# eCog100_ESP8266_Wifi.net
KiCad netlist of a schematic drawn in EAGLE
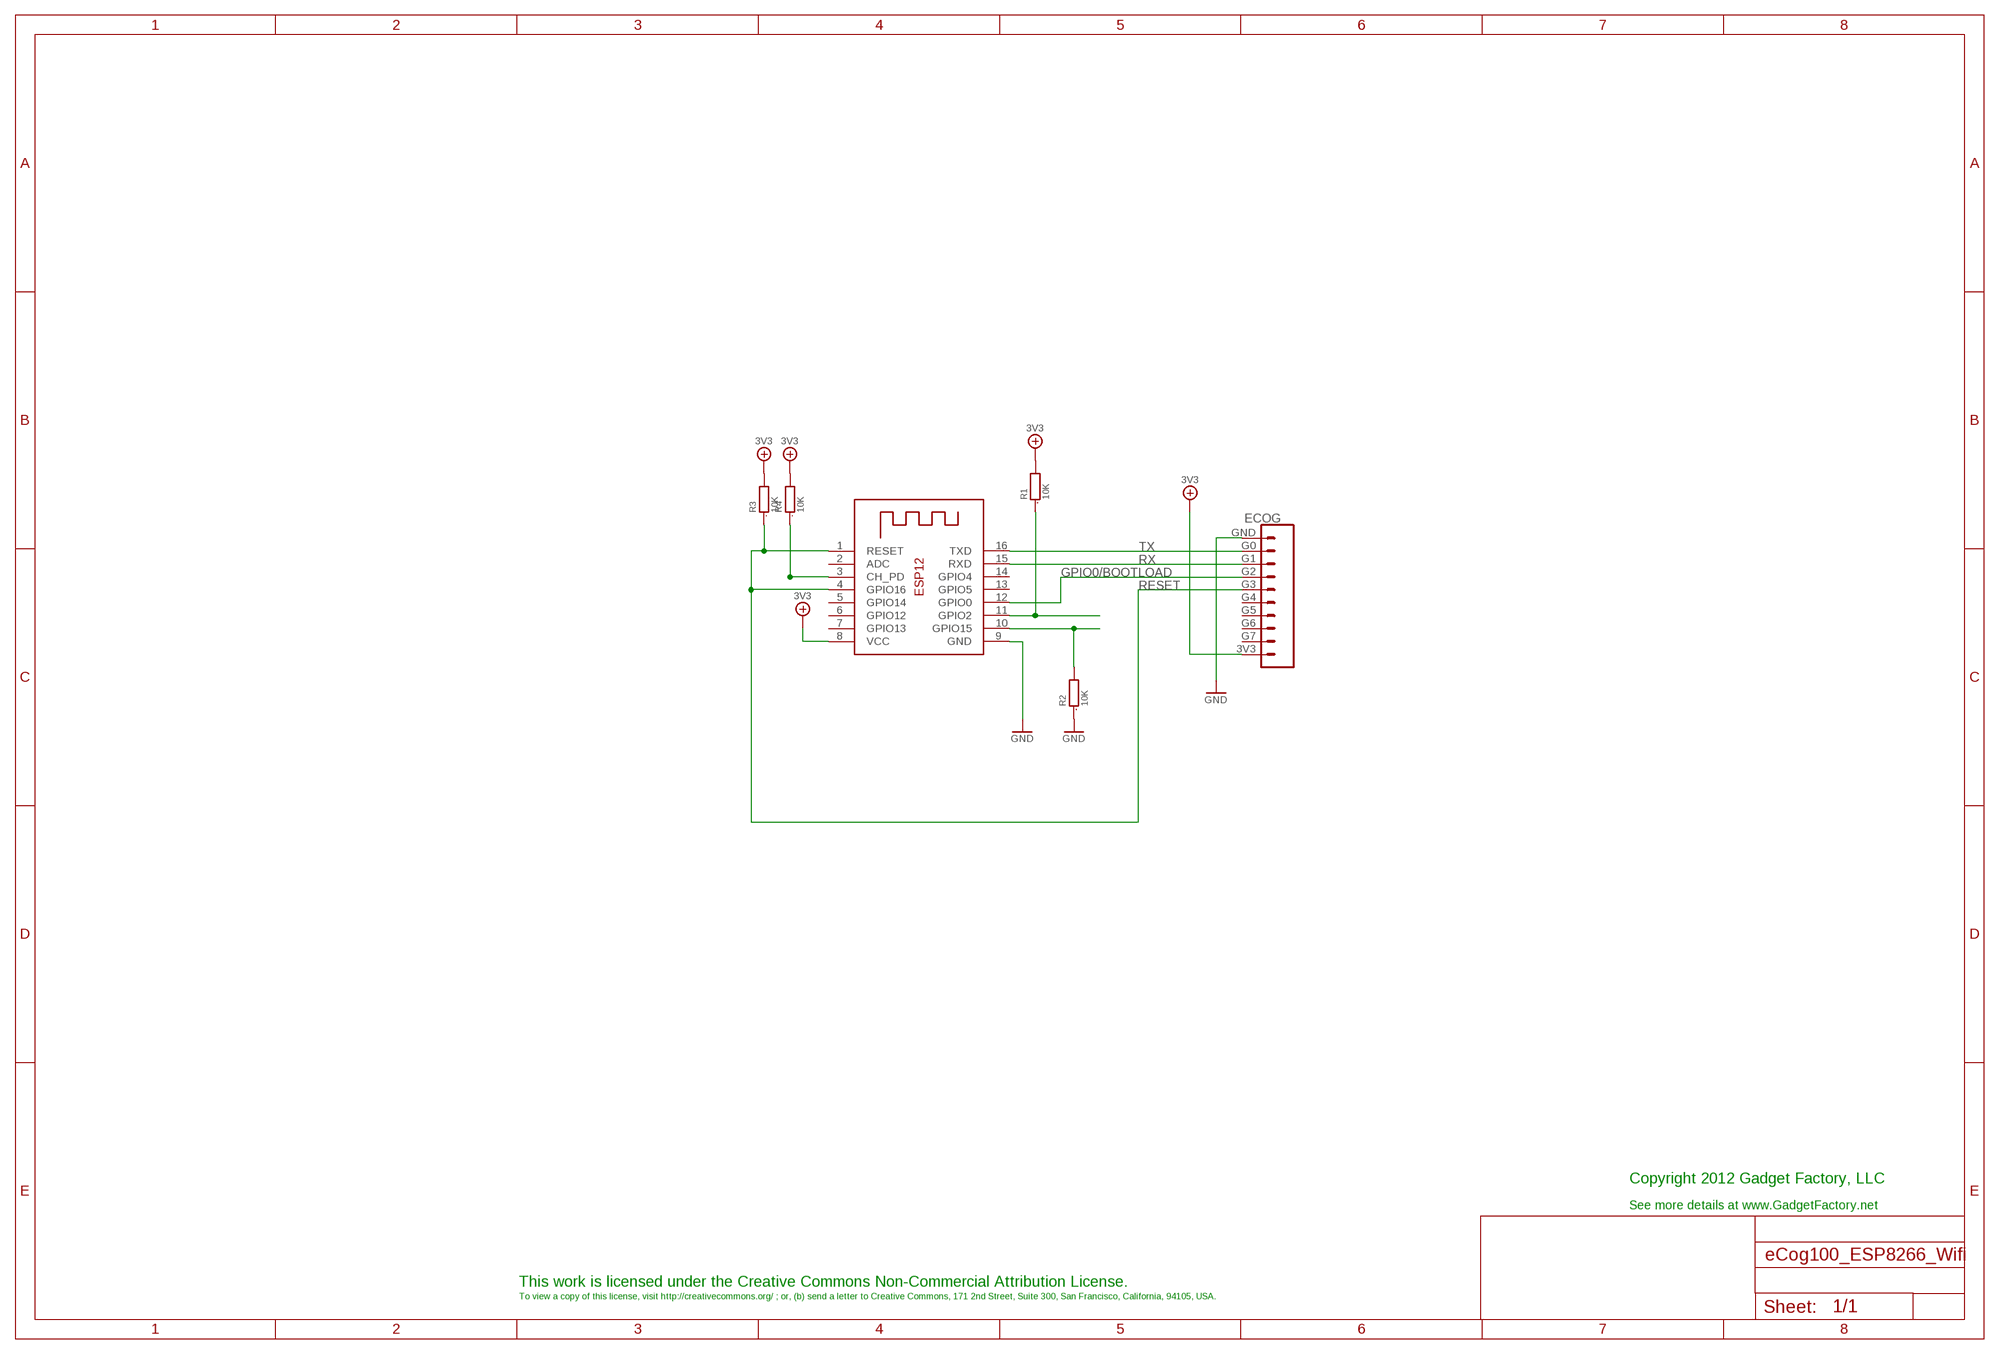
[diagram p0: schematic, sheet 1]

(export (version "E")
  (design (tool "Eeschema 10.0.6"))
  (components
    (comp (ref "ECOG")
      (value "ECOG_GENERAL_ROWECOG_GENERAL_SMD")
      (footprint "eagle-import:ECOG_GENERAL_SMD")
      (libsource (lib "eagle-import") (part "ECOG_GENERAL_ROWECOG_GENERAL_SMD"))
    )
    (comp (ref "R1")
      (value "10K")
      (footprint "eagle-import:0805")
      (libsource (lib "eagle-import") (part "R0805"))
    )
    (comp (ref "R2")
      (value "10K")
      (footprint "eagle-import:0805")
      (libsource (lib "eagle-import") (part "R0805"))
    )
    (comp (ref "R3")
      (value "10K")
      (footprint "eagle-import:0805")
      (libsource (lib "eagle-import") (part "R0805"))
    )
    (comp (ref "R4")
      (value "10K")
      (footprint "eagle-import:0805")
      (libsource (lib "eagle-import") (part "R0805"))
    )
    (comp (ref "X1")
      (value "ESP-12")
      (footprint "eagle-import:ESP-12")
      (libsource (lib "eagle-import") (part "ESP-12"))
    )
  )
  (nets
    (net (code "1") (name "/GPIO0{slash}BOOTLOAD") (class "Default")
      (node (ref "ECOG") (pin "G2") (pinfunction "G2_G2") (pintype "passive"))
      (node (ref "X1") (pin "12") (pinfunction "GPIO0_12") (pintype "bidirectional"))
    )
    (net (code "2") (name "/RESET") (class "Default")
      (node (ref "ECOG") (pin "G3") (pinfunction "G3_G3") (pintype "passive"))
      (node (ref "R3") (pin "1") (pinfunction "1_1") (pintype "passive"))
      (node (ref "X1") (pin "1") (pinfunction "RESET_1") (pintype "input"))
      (node (ref "X1") (pin "4") (pinfunction "GPIO16_4") (pintype "bidirectional"))
    )
    (net (code "3") (name "/RX") (class "Default")
      (node (ref "ECOG") (pin "G1") (pinfunction "G1_G1") (pintype "passive"))
      (node (ref "X1") (pin "15") (pinfunction "RXD_15") (pintype "input"))
    )
    (net (code "4") (name "/TX") (class "Default")
      (node (ref "ECOG") (pin "G0") (pinfunction "G0_G0") (pintype "passive"))
      (node (ref "X1") (pin "16") (pinfunction "TXD_16") (pintype "output"))
    )
    (net (code "5") (name "3V3") (class "Default")
      (node (ref "ECOG") (pin "3V3") (pinfunction "3V3_3V3") (pintype "power_in"))
      (node (ref "R1") (pin "2") (pinfunction "2_2") (pintype "passive"))
      (node (ref "R3") (pin "2") (pinfunction "2_2") (pintype "passive"))
      (node (ref "R4") (pin "2") (pinfunction "2_2") (pintype "passive"))
      (node (ref "X1") (pin "8") (pinfunction "VCC_8") (pintype "power_in"))
    )
    (net (code "6") (name "GND") (class "Default")
      (node (ref "ECOG") (pin "GND") (pinfunction "GND_GND") (pintype "power_in"))
      (node (ref "R2") (pin "1") (pinfunction "1_1") (pintype "passive"))
      (node (ref "X1") (pin "9") (pinfunction "GND_9") (pintype "power_in"))
    )
    (net (code "7") (name "Net-(X1-CH_PD)") (class "Default")
      (node (ref "R4") (pin "1") (pinfunction "1_1") (pintype "passive"))
      (node (ref "X1") (pin "3") (pinfunction "CH_PD_3") (pintype "input"))
    )
    (net (code "8") (name "Net-(X1-GPIO2)") (class "Default")
      (node (ref "R1") (pin "1") (pinfunction "1_1") (pintype "passive"))
      (node (ref "X1") (pin "11") (pinfunction "GPIO2_11") (pintype "bidirectional"))
    )
    (net (code "9") (name "Net-(X1-GPIO15)") (class "Default")
      (node (ref "R2") (pin "2") (pinfunction "2_2") (pintype "passive"))
      (node (ref "X1") (pin "10") (pinfunction "GPIO15_10") (pintype "bidirectional"))
    )
    (net (code "10") (name "unconnected-(ECOG-PadG4)") (class "Default")
      (node (ref "ECOG") (pin "G4") (pinfunction "G4_G4") (pintype "passive"))
    )
    (net (code "11") (name "unconnected-(ECOG-PadG5)") (class "Default")
      (node (ref "ECOG") (pin "G5") (pinfunction "G5_G5") (pintype "passive"))
    )
    (net (code "12") (name "unconnected-(ECOG-PadG6)") (class "Default")
      (node (ref "ECOG") (pin "G6") (pinfunction "G6_G6") (pintype "passive"))
    )
    (net (code "13") (name "unconnected-(ECOG-PadG7)") (class "Default")
      (node (ref "ECOG") (pin "G7") (pinfunction "G7_G7") (pintype "passive"))
    )
    (net (code "14") (name "unconnected-(X1-ADC-Pad2)") (class "Default")
      (node (ref "X1") (pin "2") (pinfunction "ADC_2") (pintype "passive"))
    )
    (net (code "15") (name "unconnected-(X1-GPIO4-Pad14)") (class "Default")
      (node (ref "X1") (pin "14") (pinfunction "GPIO4_14") (pintype "bidirectional"))
    )
    (net (code "16") (name "unconnected-(X1-GPIO5-Pad13)") (class "Default")
      (node (ref "X1") (pin "13") (pinfunction "GPIO5_13") (pintype "bidirectional"))
    )
    (net (code "17") (name "unconnected-(X1-GPIO12-Pad6)") (class "Default")
      (node (ref "X1") (pin "6") (pinfunction "GPIO12_6") (pintype "bidirectional"))
    )
    (net (code "18") (name "unconnected-(X1-GPIO13-Pad7)") (class "Default")
      (node (ref "X1") (pin "7") (pinfunction "GPIO13_7") (pintype "bidirectional"))
    )
    (net (code "19") (name "unconnected-(X1-GPIO14-Pad5)") (class "Default")
      (node (ref "X1") (pin "5") (pinfunction "GPIO14_5") (pintype "bidirectional"))
    )
  )
)
